# Connectors.net
KiCad netlist of a schematic drawn in Altium Designer
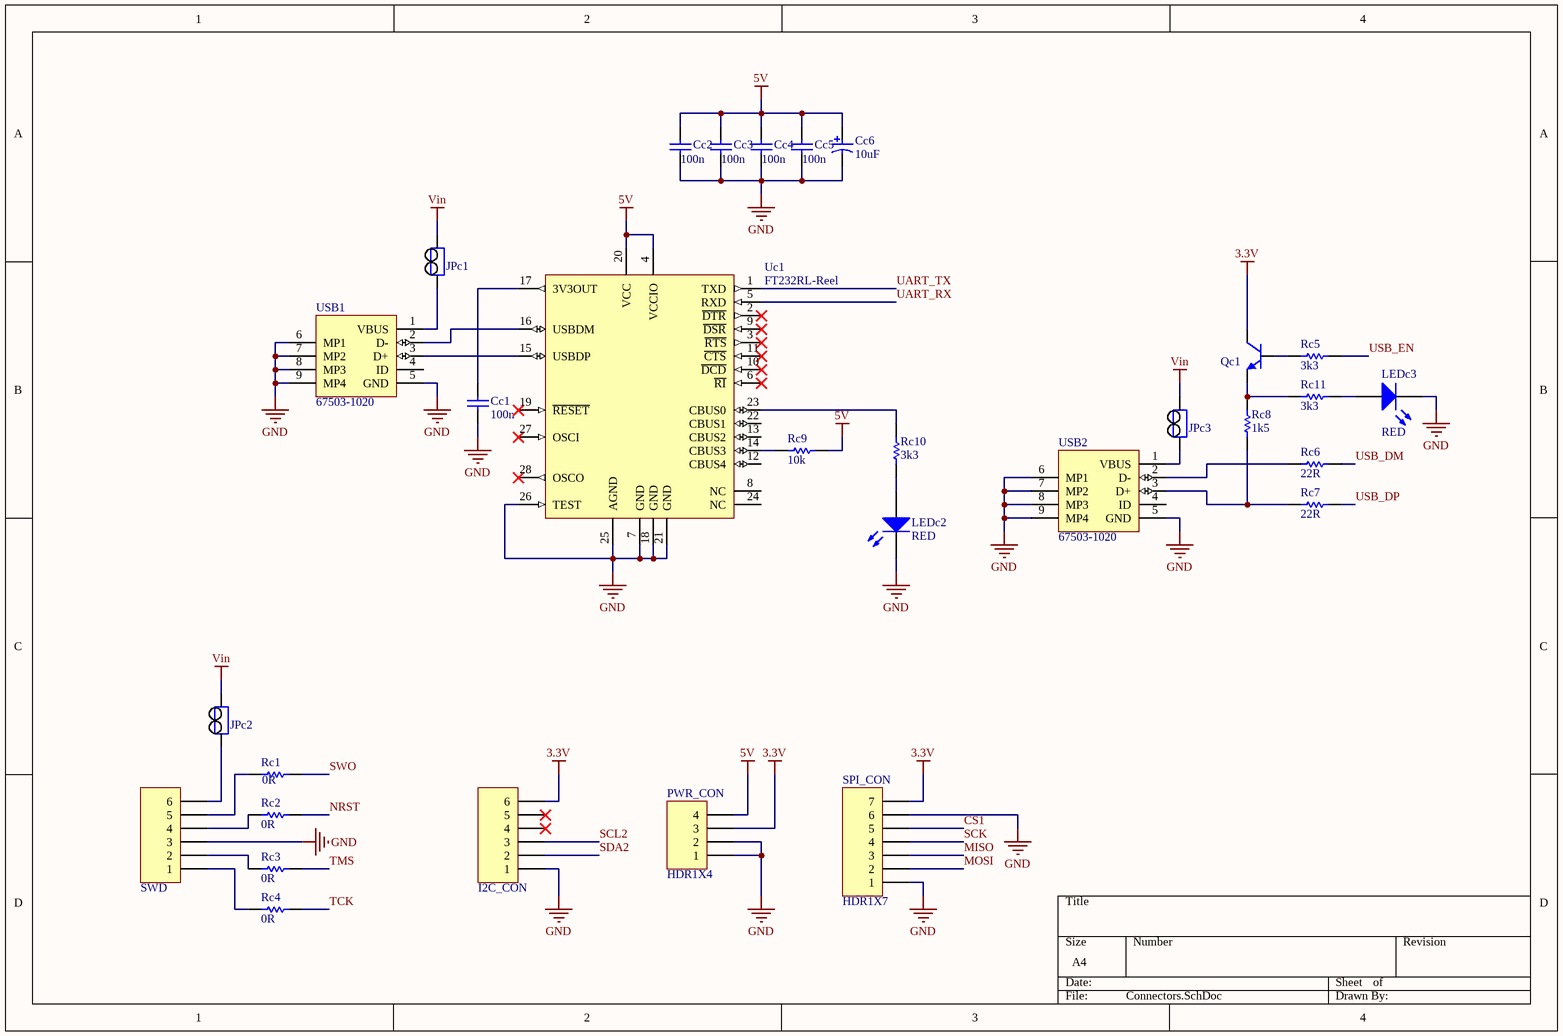
[diagram p0: Connectors.SchDoc]

(export (version "E")
  (design (tool "Eeschema 10.0.6"))
  (components
    (comp (ref "Cc1")
      (value "100n")
      (footprint "CAPC0603(1608)100_L")
      (description "0603 (1608 Metric) Chip Capacitor")
      (libsource (lib "Altium Content Vault") (part "CAP_5"))
    )
    (comp (ref "Cc2")
      (value "100n")
      (footprint "CAPC0603(1608)100_L")
      (description "0603 (1608 Metric) Chip Capacitor")
      (libsource (lib "Altium Content Vault") (part "CAP_5"))
    )
    (comp (ref "Cc3")
      (value "100n")
      (footprint "CAPC0603(1608)100_L")
      (description "0603 (1608 Metric) Chip Capacitor")
      (libsource (lib "Altium Content Vault") (part "CAP_5"))
    )
    (comp (ref "Cc4")
      (value "100n")
      (footprint "CAPC0603(1608)100_L")
      (description "0603 (1608 Metric) Chip Capacitor")
      (libsource (lib "Altium Content Vault") (part "CAP_5"))
    )
    (comp (ref "Cc5")
      (value "100n")
      (footprint "CAPC0603(1608)100_L")
      (description "0603 (1608 Metric) Chip Capacitor")
      (libsource (lib "Altium Content Vault") (part "CAP_5"))
    )
    (comp (ref "Cc6")
      (value "10uF")
      (footprint "CAPMP3217X18-T_V")
      (description "Standard Tantalum, 1 uF, +/- 10%, 35 V, -55 to 125 degC, 2-Pin SMD (1206), RoHS, Tape and Reel")
      (libsource (lib "Altium Content Vault") (part "CAP-P-2"))
    )
    (comp (ref "I2C_CON")
      (value "HDR1X6")
      (footprint "HDR1X6")
      (description "Header, 6-Pin")
      (fields (field (name "PUBLISHER") "Altium Limited"))
      (libsource (lib "Library_Altium") (part "HDR1X6"))
    )
    (comp (ref "JPc1")
      (value "Jumper")
      (footprint "HDR1X2 - JP")
      (description "Jumper, 2-Pin")
      (libsource (lib "Library_Altium") (part "Jumper_2"))
    )
    (comp (ref "JPc2")
      (value "Jumper")
      (footprint "HDR1X2 - JP")
      (description "Jumper, 2-Pin")
      (libsource (lib "Library_Altium") (part "Jumper_2"))
    )
    (comp (ref "JPc3")
      (value "Jumper")
      (footprint "HDR1X2 - JP")
      (description "Jumper, 2-Pin")
      (libsource (lib "Library_Altium") (part "Jumper_2"))
    )
    (comp (ref "LEDc2")
      (value "RED")
      (footprint "0805_DIODE")
      (description "Light-emitting diode")
      (libsource (lib "Library_Altium") (part "LED"))
    )
    (comp (ref "LEDc3")
      (value "RED")
      (footprint "0805_DIODE")
      (description "Light-emitting diode")
      (libsource (lib "Library_Altium") (part "LED"))
    )
    (comp (ref "PWR_CON")
      (value "HDR1X4")
      (footprint "HDR1X4")
      (description "Header, 4-Pin")
      (fields (field (name "PUBLISHER") "Altium Limited"))
      (libsource (lib "Library_Altium") (part "HDR1X4"))
    )
    (comp (ref "Qc1")
      (value "BC817-25")
      (footprint "SOT23_N")
      (description "NPN General-purpose Transistor")
      (fields (field (name "PUBLISHER") "Altium Limited"))
      (libsource (lib "Library_Altium") (part "BC817-25"))
    )
    (comp (ref "Rc1")
      (value "0R")
      (footprint "RESC0603(1608)_L")
      (description "0603 (1608 Metric) Chip Resistor")
      (libsource (lib "Altium Content Vault") (part "RES_3"))
    )
    (comp (ref "Rc2")
      (value "0R")
      (footprint "RESC0603(1608)_L")
      (description "0603 (1608 Metric) Chip Resistor")
      (libsource (lib "Altium Content Vault") (part "RES_3"))
    )
    (comp (ref "Rc3")
      (value "0R")
      (footprint "RESC0603(1608)_L")
      (description "0603 (1608 Metric) Chip Resistor")
      (libsource (lib "Altium Content Vault") (part "RES_3"))
    )
    (comp (ref "Rc4")
      (value "0R")
      (footprint "RESC0603(1608)_L")
      (description "0603 (1608 Metric) Chip Resistor")
      (libsource (lib "Altium Content Vault") (part "RES_3"))
    )
    (comp (ref "Rc5")
      (value "3k3")
      (footprint "RESC0603(1608)_L")
      (description "0603 (1608 Metric) Chip Resistor")
      (libsource (lib "Altium Content Vault") (part "RES_3"))
    )
    (comp (ref "Rc6")
      (value "22R")
      (footprint "RESC0603(1608)_L")
      (description "0603 (1608 Metric) Chip Resistor")
      (libsource (lib "Altium Content Vault") (part "RES_3"))
    )
    (comp (ref "Rc7")
      (value "22R")
      (footprint "RESC0603(1608)_L")
      (description "0603 (1608 Metric) Chip Resistor")
      (libsource (lib "Altium Content Vault") (part "RES_3"))
    )
    (comp (ref "Rc8")
      (value "1k5")
      (footprint "RESC0603(1608)_L")
      (description "0603 (1608 Metric) Chip Resistor")
      (libsource (lib "Altium Content Vault") (part "RES_3"))
    )
    (comp (ref "Rc9")
      (value "10k")
      (footprint "RESC0603(1608)_L")
      (description "0603 (1608 Metric) Chip Resistor")
      (libsource (lib "Altium Content Vault") (part "RES_3"))
    )
    (comp (ref "Rc10")
      (value "3k3")
      (footprint "RESC0603(1608)_L")
      (description "0603 (1608 Metric) Chip Resistor")
      (libsource (lib "Altium Content Vault") (part "RES_3"))
    )
    (comp (ref "Rc11")
      (value "3k3")
      (footprint "RESC0603(1608)_L")
      (description "0603 (1608 Metric) Chip Resistor")
      (libsource (lib "Altium Content Vault") (part "RES_3"))
    )
    (comp (ref "SPI_CON")
      (value "HDR1X7")
      (footprint "HDR1X7")
      (description "Header, 7-Pin")
      (fields (field (name "PUBLISHER") "Altium Limited"))
      (libsource (lib "Library_Altium") (part "HDR1X7"))
    )
    (comp (ref "SWD")
      (value "HDR1X6")
      (footprint "HDR1X6")
      (description "Header, 6-Pin")
      (fields (field (name "PUBLISHER") "Altium Limited"))
      (libsource (lib "Library_Altium") (part "HDR1X6"))
    )
    (comp (ref "Uc1")
      (value "FT232RL-Reel")
      (footprint "SSOP-28_L")
      (description "USB UART Asynchronous Serial Data Transfer Chip, 28-pin SSOP, Tape and Reel")
      (fields (field (name "MANUFACTURER") "FTDI"))
      (libsource (lib "Altium Content Vault") (part "COM-UART-FT232R-IL28"))
    )
    (comp (ref "USB1")
      (value "67503-1020")
      (footprint "MOLX-67503-1020_V")
      (description "USB, MINI, SMD, RA KME04-USBMU03A01")
      (fields (field (name "MANUFACTURER") "Molex"))
      (libsource (lib "Altium Content Vault") (part "CMP-0411-00002-1"))
    )
    (comp (ref "USB2")
      (value "67503-1020")
      (footprint "MOLX-67503-1020_V")
      (description "USB, MINI, SMD, RA KME04-USBMU03A01")
      (fields (field (name "MANUFACTURER") "Molex"))
      (libsource (lib "Altium Content Vault") (part "CMP-0411-00002-1"))
    )
  )
  (nets
    (net (code "1") (name "/CS1") (class "Default")
      (node (ref "SPI_CON") (pin "5") (pinfunction "5_5") (pintype "passive"))
    )
    (net (code "2") (name "/MISO") (class "Default")
      (node (ref "SPI_CON") (pin "3") (pinfunction "3_3") (pintype "passive"))
    )
    (net (code "3") (name "/MOSI") (class "Default")
      (node (ref "SPI_CON") (pin "2") (pinfunction "2_2") (pintype "passive"))
    )
    (net (code "4") (name "/NRST") (class "Default")
      (node (ref "Rc2") (pin "2") (pinfunction "2_2") (pintype "passive"))
    )
    (net (code "5") (name "/SCK") (class "Default")
      (node (ref "SPI_CON") (pin "4") (pinfunction "4_4") (pintype "passive"))
    )
    (net (code "6") (name "/SCL2") (class "Default")
      (node (ref "I2C_CON") (pin "3") (pinfunction "3_3") (pintype "passive"))
    )
    (net (code "7") (name "/SDA2") (class "Default")
      (node (ref "I2C_CON") (pin "2") (pinfunction "2_2") (pintype "passive"))
    )
    (net (code "8") (name "/SWO") (class "Default")
      (node (ref "Rc1") (pin "2") (pinfunction "2_2") (pintype "passive"))
    )
    (net (code "9") (name "/TCK") (class "Default")
      (node (ref "Rc4") (pin "2") (pinfunction "2_2") (pintype "passive"))
    )
    (net (code "10") (name "/TMS") (class "Default")
      (node (ref "Rc3") (pin "2") (pinfunction "2_2") (pintype "passive"))
    )
    (net (code "11") (name "/UART_RX") (class "Default")
      (node (ref "Uc1") (pin "5") (pinfunction "RXD_5") (pintype "input"))
    )
    (net (code "12") (name "/UART_TX") (class "Default")
      (node (ref "Uc1") (pin "1") (pinfunction "TXD_1") (pintype "output"))
    )
    (net (code "13") (name "/USB_DM") (class "Default")
      (node (ref "Rc6") (pin "2") (pinfunction "2_2") (pintype "passive"))
    )
    (net (code "14") (name "/USB_DP") (class "Default")
      (node (ref "Rc7") (pin "2") (pinfunction "2_2") (pintype "passive"))
    )
    (net (code "15") (name "/USB_EN") (class "Default")
      (node (ref "Rc5") (pin "1") (pinfunction "1_1") (pintype "passive"))
    )
    (net (code "16") (name "3.3V") (class "Default")
      (node (ref "I2C_CON") (pin "6") (pinfunction "6_6") (pintype "passive"))
      (node (ref "PWR_CON") (pin "3") (pinfunction "3_3") (pintype "passive"))
      (node (ref "Qc1") (pin "3") (pinfunction "C_3") (pintype "passive"))
      (node (ref "SPI_CON") (pin "7") (pinfunction "7_7") (pintype "passive"))
    )
    (net (code "17") (name "5V") (class "Default")
      (node (ref "Cc2") (pin "2") (pinfunction "2_2") (pintype "passive"))
      (node (ref "Cc3") (pin "2") (pinfunction "2_2") (pintype "passive"))
      (node (ref "Cc4") (pin "2") (pinfunction "2_2") (pintype "passive"))
      (node (ref "Cc5") (pin "2") (pinfunction "2_2") (pintype "passive"))
      (node (ref "Cc6") (pin "1") (pinfunction "1_1") (pintype "passive"))
      (node (ref "PWR_CON") (pin "4") (pinfunction "4_4") (pintype "passive"))
      (node (ref "Rc9") (pin "1") (pinfunction "1_1") (pintype "passive"))
      (node (ref "Uc1") (pin "20") (pinfunction "VCC_20") (pintype "power_in"))
      (node (ref "Uc1") (pin "4") (pinfunction "VCCIO_4") (pintype "power_in"))
    )
    (net (code "18") (name "GND") (class "Default")
      (node (ref "Cc1") (pin "1") (pinfunction "1_1") (pintype "passive"))
      (node (ref "Cc2") (pin "1") (pinfunction "1_1") (pintype "passive"))
      (node (ref "Cc3") (pin "1") (pinfunction "1_1") (pintype "passive"))
      (node (ref "Cc4") (pin "1") (pinfunction "1_1") (pintype "passive"))
      (node (ref "Cc5") (pin "1") (pinfunction "1_1") (pintype "passive"))
      (node (ref "Cc6") (pin "2") (pinfunction "2_2") (pintype "passive"))
      (node (ref "I2C_CON") (pin "1") (pinfunction "1_1") (pintype "passive"))
      (node (ref "LEDc2") (pin "2") (pinfunction "K_2") (pintype "passive"))
      (node (ref "LEDc3") (pin "2") (pinfunction "K_2") (pintype "passive"))
      (node (ref "PWR_CON") (pin "1") (pinfunction "1_1") (pintype "passive"))
      (node (ref "PWR_CON") (pin "2") (pinfunction "2_2") (pintype "passive"))
      (node (ref "SPI_CON") (pin "1") (pinfunction "1_1") (pintype "passive"))
      (node (ref "SPI_CON") (pin "6") (pinfunction "6_6") (pintype "passive"))
      (node (ref "SWD") (pin "3") (pinfunction "3_3") (pintype "passive"))
      (node (ref "USB1") (pin "5") (pinfunction "GND_5") (pintype "power_in"))
      (node (ref "USB1") (pin "6") (pinfunction "MP1_6") (pintype "passive"))
      (node (ref "USB1") (pin "7") (pinfunction "MP2_7") (pintype "passive"))
      (node (ref "USB1") (pin "8") (pinfunction "MP3_8") (pintype "passive"))
      (node (ref "USB1") (pin "9") (pinfunction "MP4_9") (pintype "passive"))
      (node (ref "USB2") (pin "5") (pinfunction "GND_5") (pintype "power_in"))
      (node (ref "USB2") (pin "6") (pinfunction "MP1_6") (pintype "passive"))
      (node (ref "USB2") (pin "7") (pinfunction "MP2_7") (pintype "passive"))
      (node (ref "USB2") (pin "8") (pinfunction "MP3_8") (pintype "passive"))
      (node (ref "USB2") (pin "9") (pinfunction "MP4_9") (pintype "passive"))
      (node (ref "Uc1") (pin "18") (pinfunction "GND_18") (pintype "power_in"))
      (node (ref "Uc1") (pin "21") (pinfunction "GND_21") (pintype "power_in"))
      (node (ref "Uc1") (pin "25") (pinfunction "AGND_25") (pintype "power_in"))
      (node (ref "Uc1") (pin "26") (pinfunction "TEST_26") (pintype "input"))
      (node (ref "Uc1") (pin "7") (pinfunction "GND_7") (pintype "power_in"))
    )
    (net (code "19") (name "Net-(JPc2-Pad1)") (class "Default")
      (node (ref "JPc2") (pin "1") (pinfunction "1_1") (pintype "passive"))
      (node (ref "SWD") (pin "6") (pinfunction "6_6") (pintype "passive"))
    )
    (net (code "20") (name "Net-(LEDc2-A)") (class "Default")
      (node (ref "LEDc2") (pin "1") (pinfunction "A_1") (pintype "passive"))
      (node (ref "Rc10") (pin "1") (pinfunction "1_1") (pintype "passive"))
    )
    (net (code "21") (name "Net-(LEDc3-A)") (class "Default")
      (node (ref "LEDc3") (pin "1") (pinfunction "A_1") (pintype "passive"))
      (node (ref "Rc11") (pin "1") (pinfunction "1_1") (pintype "passive"))
    )
    (net (code "22") (name "Net-(Qc1-B)") (class "Default")
      (node (ref "Qc1") (pin "1") (pinfunction "B_1") (pintype "passive"))
      (node (ref "Rc5") (pin "2") (pinfunction "2_2") (pintype "passive"))
    )
    (net (code "23") (name "Net-(Qc1-E)") (class "Default")
      (node (ref "Qc1") (pin "2") (pinfunction "E_2") (pintype "passive"))
      (node (ref "Rc11") (pin "2") (pinfunction "2_2") (pintype "passive"))
      (node (ref "Rc8") (pin "2") (pinfunction "2_2") (pintype "passive"))
    )
    (net (code "24") (name "Net-(Rc1-Pad1)") (class "Default")
      (node (ref "Rc1") (pin "1") (pinfunction "1_1") (pintype "passive"))
      (node (ref "SWD") (pin "5") (pinfunction "5_5") (pintype "passive"))
    )
    (net (code "25") (name "Net-(Rc2-Pad1)") (class "Default")
      (node (ref "Rc2") (pin "1") (pinfunction "1_1") (pintype "passive"))
      (node (ref "SWD") (pin "4") (pinfunction "4_4") (pintype "passive"))
    )
    (net (code "26") (name "Net-(Rc3-Pad1)") (class "Default")
      (node (ref "Rc3") (pin "1") (pinfunction "1_1") (pintype "passive"))
      (node (ref "SWD") (pin "2") (pinfunction "2_2") (pintype "passive"))
    )
    (net (code "27") (name "Net-(Rc4-Pad1)") (class "Default")
      (node (ref "Rc4") (pin "1") (pinfunction "1_1") (pintype "passive"))
      (node (ref "SWD") (pin "1") (pinfunction "1_1") (pintype "passive"))
    )
    (net (code "28") (name "Net-(USB1-D+)") (class "Default")
      (node (ref "USB1") (pin "3") (pinfunction "D+_3") (pintype "bidirectional"))
      (node (ref "Uc1") (pin "15") (pinfunction "USBDP_15") (pintype "bidirectional"))
    )
    (net (code "29") (name "Net-(USB1-D-)") (class "Default")
      (node (ref "USB1") (pin "2") (pinfunction "D-_2") (pintype "bidirectional"))
      (node (ref "Uc1") (pin "16") (pinfunction "USBDM_16") (pintype "bidirectional"))
    )
    (net (code "30") (name "Net-(USB1-VBUS)") (class "Default")
      (node (ref "JPc1") (pin "1") (pinfunction "1_1") (pintype "passive"))
      (node (ref "USB1") (pin "1") (pinfunction "VBUS_1") (pintype "power_in"))
    )
    (net (code "31") (name "Net-(USB2-D+)") (class "Default")
      (node (ref "Rc7") (pin "1") (pinfunction "1_1") (pintype "passive"))
      (node (ref "Rc8") (pin "1") (pinfunction "1_1") (pintype "passive"))
      (node (ref "USB2") (pin "3") (pinfunction "D+_3") (pintype "bidirectional"))
    )
    (net (code "32") (name "Net-(USB2-D-)") (class "Default")
      (node (ref "Rc6") (pin "1") (pinfunction "1_1") (pintype "passive"))
      (node (ref "USB2") (pin "2") (pinfunction "D-_2") (pintype "bidirectional"))
    )
    (net (code "33") (name "Net-(USB2-VBUS)") (class "Default")
      (node (ref "JPc3") (pin "1") (pinfunction "1_1") (pintype "passive"))
      (node (ref "USB2") (pin "1") (pinfunction "VBUS_1") (pintype "power_in"))
    )
    (net (code "34") (name "Net-(Uc1-3V3OUT)") (class "Default")
      (node (ref "Cc1") (pin "2") (pinfunction "2_2") (pintype "passive"))
      (node (ref "Uc1") (pin "17") (pinfunction "3V3OUT_17") (pintype "output"))
    )
    (net (code "35") (name "Net-(Uc1-CBUS0)") (class "Default")
      (node (ref "Rc10") (pin "2") (pinfunction "2_2") (pintype "passive"))
      (node (ref "Uc1") (pin "23") (pinfunction "CBUS0_23") (pintype "bidirectional"))
    )
    (net (code "36") (name "Net-(Uc1-CBUS3)") (class "Default")
      (node (ref "Rc9") (pin "2") (pinfunction "2_2") (pintype "passive"))
      (node (ref "Uc1") (pin "14") (pinfunction "CBUS3_14") (pintype "bidirectional"))
    )
    (net (code "37") (name "Vin") (class "Default")
      (node (ref "JPc1") (pin "2") (pinfunction "2_2") (pintype "passive"))
      (node (ref "JPc2") (pin "2") (pinfunction "2_2") (pintype "passive"))
      (node (ref "JPc3") (pin "2") (pinfunction "2_2") (pintype "passive"))
    )
    (net (code "38") (name "unconnected-(I2C_CON-Pad4)") (class "Default")
      (node (ref "I2C_CON") (pin "4") (pinfunction "4_4") (pintype "passive+no_connect"))
    )
    (net (code "39") (name "unconnected-(I2C_CON-Pad5)") (class "Default")
      (node (ref "I2C_CON") (pin "5") (pinfunction "5_5") (pintype "passive+no_connect"))
    )
    (net (code "40") (name "unconnected-(USB1-ID-Pad4)") (class "Default")
      (node (ref "USB1") (pin "4") (pinfunction "ID_4") (pintype "passive"))
    )
    (net (code "41") (name "unconnected-(USB2-ID-Pad4)") (class "Default")
      (node (ref "USB2") (pin "4") (pinfunction "ID_4") (pintype "passive"))
    )
    (net (code "42") (name "unconnected-(Uc1-CBUS1-Pad22)") (class "Default")
      (node (ref "Uc1") (pin "22") (pinfunction "CBUS1_22") (pintype "bidirectional"))
    )
    (net (code "43") (name "unconnected-(Uc1-CBUS2-Pad13)") (class "Default")
      (node (ref "Uc1") (pin "13") (pinfunction "CBUS2_13") (pintype "bidirectional"))
    )
    (net (code "44") (name "unconnected-(Uc1-CBUS4-Pad12)") (class "Default")
      (node (ref "Uc1") (pin "12") (pinfunction "CBUS4_12") (pintype "bidirectional"))
    )
    (net (code "45") (name "unconnected-(Uc1-NC-Pad8)") (class "Default")
      (node (ref "Uc1") (pin "8") (pinfunction "NC_8") (pintype "passive"))
    )
    (net (code "46") (name "unconnected-(Uc1-NC-Pad24)") (class "Default")
      (node (ref "Uc1") (pin "24") (pinfunction "NC_24") (pintype "passive"))
    )
    (net (code "47") (name "unconnected-(Uc1-OSCI-Pad27)") (class "Default")
      (node (ref "Uc1") (pin "27") (pinfunction "OSCI_27") (pintype "input+no_connect"))
    )
    (net (code "48") (name "unconnected-(Uc1-OSCO-Pad28)") (class "Default")
      (node (ref "Uc1") (pin "28") (pinfunction "OSCO_28") (pintype "output+no_connect"))
    )
    (net (code "49") (name "unconnected-(Uc1-~{CTS}-Pad11)") (class "Default")
      (node (ref "Uc1") (pin "11") (pinfunction "~{CTS}_11") (pintype "input+no_connect"))
    )
    (net (code "50") (name "unconnected-(Uc1-~{DCD}-Pad10)") (class "Default")
      (node (ref "Uc1") (pin "10") (pinfunction "~{DCD}_10") (pintype "input+no_connect"))
    )
    (net (code "51") (name "unconnected-(Uc1-~{DSR}-Pad9)") (class "Default")
      (node (ref "Uc1") (pin "9") (pinfunction "~{DSR}_9") (pintype "input+no_connect"))
    )
    (net (code "52") (name "unconnected-(Uc1-~{DTR}-Pad2)") (class "Default")
      (node (ref "Uc1") (pin "2") (pinfunction "~{DTR}_2") (pintype "output+no_connect"))
    )
    (net (code "53") (name "unconnected-(Uc1-~{RESET}-Pad19)") (class "Default")
      (node (ref "Uc1") (pin "19") (pinfunction "~{RESET}_19") (pintype "input+no_connect"))
    )
    (net (code "54") (name "unconnected-(Uc1-~{RI}-Pad6)") (class "Default")
      (node (ref "Uc1") (pin "6") (pinfunction "~{RI}_6") (pintype "input+no_connect"))
    )
    (net (code "55") (name "unconnected-(Uc1-~{RTS}-Pad3)") (class "Default")
      (node (ref "Uc1") (pin "3") (pinfunction "~{RTS}_3") (pintype "output+no_connect"))
    )
  )
)
